# debug_LED.net
KiCad netlist of a schematic drawn in Altium Designer
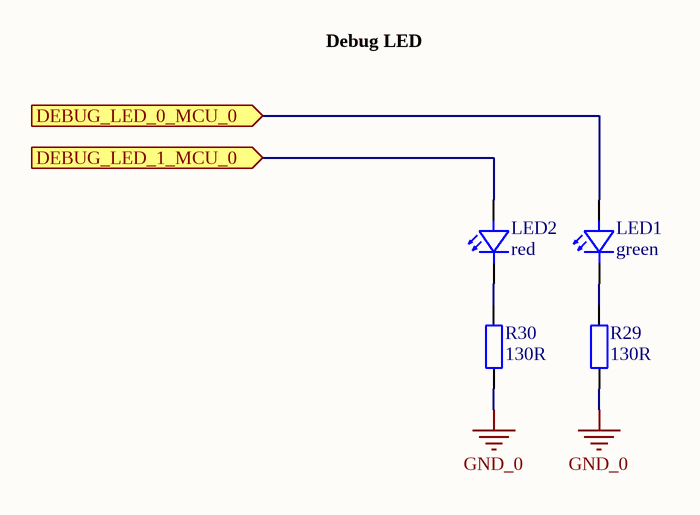
[diagram p0: debug_LED.SchDoc]

(export (version "E")
  (design (tool "Eeschema 10.0.6"))
  (components
    (comp (ref "LED1")
      (value "green")
      (footprint "LEDC1608X07N")
      (description "LED")
      (fields (field (name "PART NUMBER") "gen_LED_0603_green"))
      (libsource (lib "OE750") (part "D_LED"))
    )
    (comp (ref "LED2")
      (value "red")
      (footprint "LEDC1608X07N")
      (description "LED")
      (fields (field (name "PART NUMBER") "gen_LED_0603_red"))
      (libsource (lib "OE750") (part "D_LED"))
    )
    (comp (ref "R29")
      (value "130R")
      (footprint "0603R")
      (description "SMD Resistor 130R 0603")
      (fields (field (name "PART NUMBER") "gen_R_130R_0603") (field (name "TOLERANCE") "1%"))
      (libsource (lib "master-010106") (part "R"))
    )
    (comp (ref "R30")
      (value "130R")
      (footprint "0603R")
      (description "SMD Resistor 130R 0603")
      (fields (field (name "PART NUMBER") "gen_R_130R_0603") (field (name "TOLERANCE") "1%"))
      (libsource (lib "master-010106") (part "R"))
    )
  )
  (nets
    (net (code "1") (name "/DEBUG_LED_0_MCU_0") (class "Default")
      (node (ref "LED1") (pin "2") (pinfunction "A_2") (pintype "passive"))
    )
    (net (code "2") (name "/DEBUG_LED_1_MCU_0") (class "Default")
      (node (ref "LED2") (pin "2") (pinfunction "A_2") (pintype "passive"))
    )
    (net (code "3") (name "GND_0") (class "Default")
      (node (ref "R29") (pin "1") (pinfunction "1_1") (pintype "passive"))
      (node (ref "R30") (pin "1") (pinfunction "1_1") (pintype "passive"))
    )
    (net (code "4") (name "Net-(LED1-C)") (class "Default")
      (node (ref "LED1") (pin "1") (pinfunction "C_1") (pintype "passive"))
      (node (ref "R29") (pin "2") (pinfunction "2_2") (pintype "passive"))
    )
    (net (code "5") (name "Net-(LED2-C)") (class "Default")
      (node (ref "LED2") (pin "1") (pinfunction "C_1") (pintype "passive"))
      (node (ref "R30") (pin "2") (pinfunction "2_2") (pintype "passive"))
    )
  )
)
